# 1-Schematic_Arduino_Based_Weather_Statio.net
KiCad netlist of a schematic drawn in EasyEDA
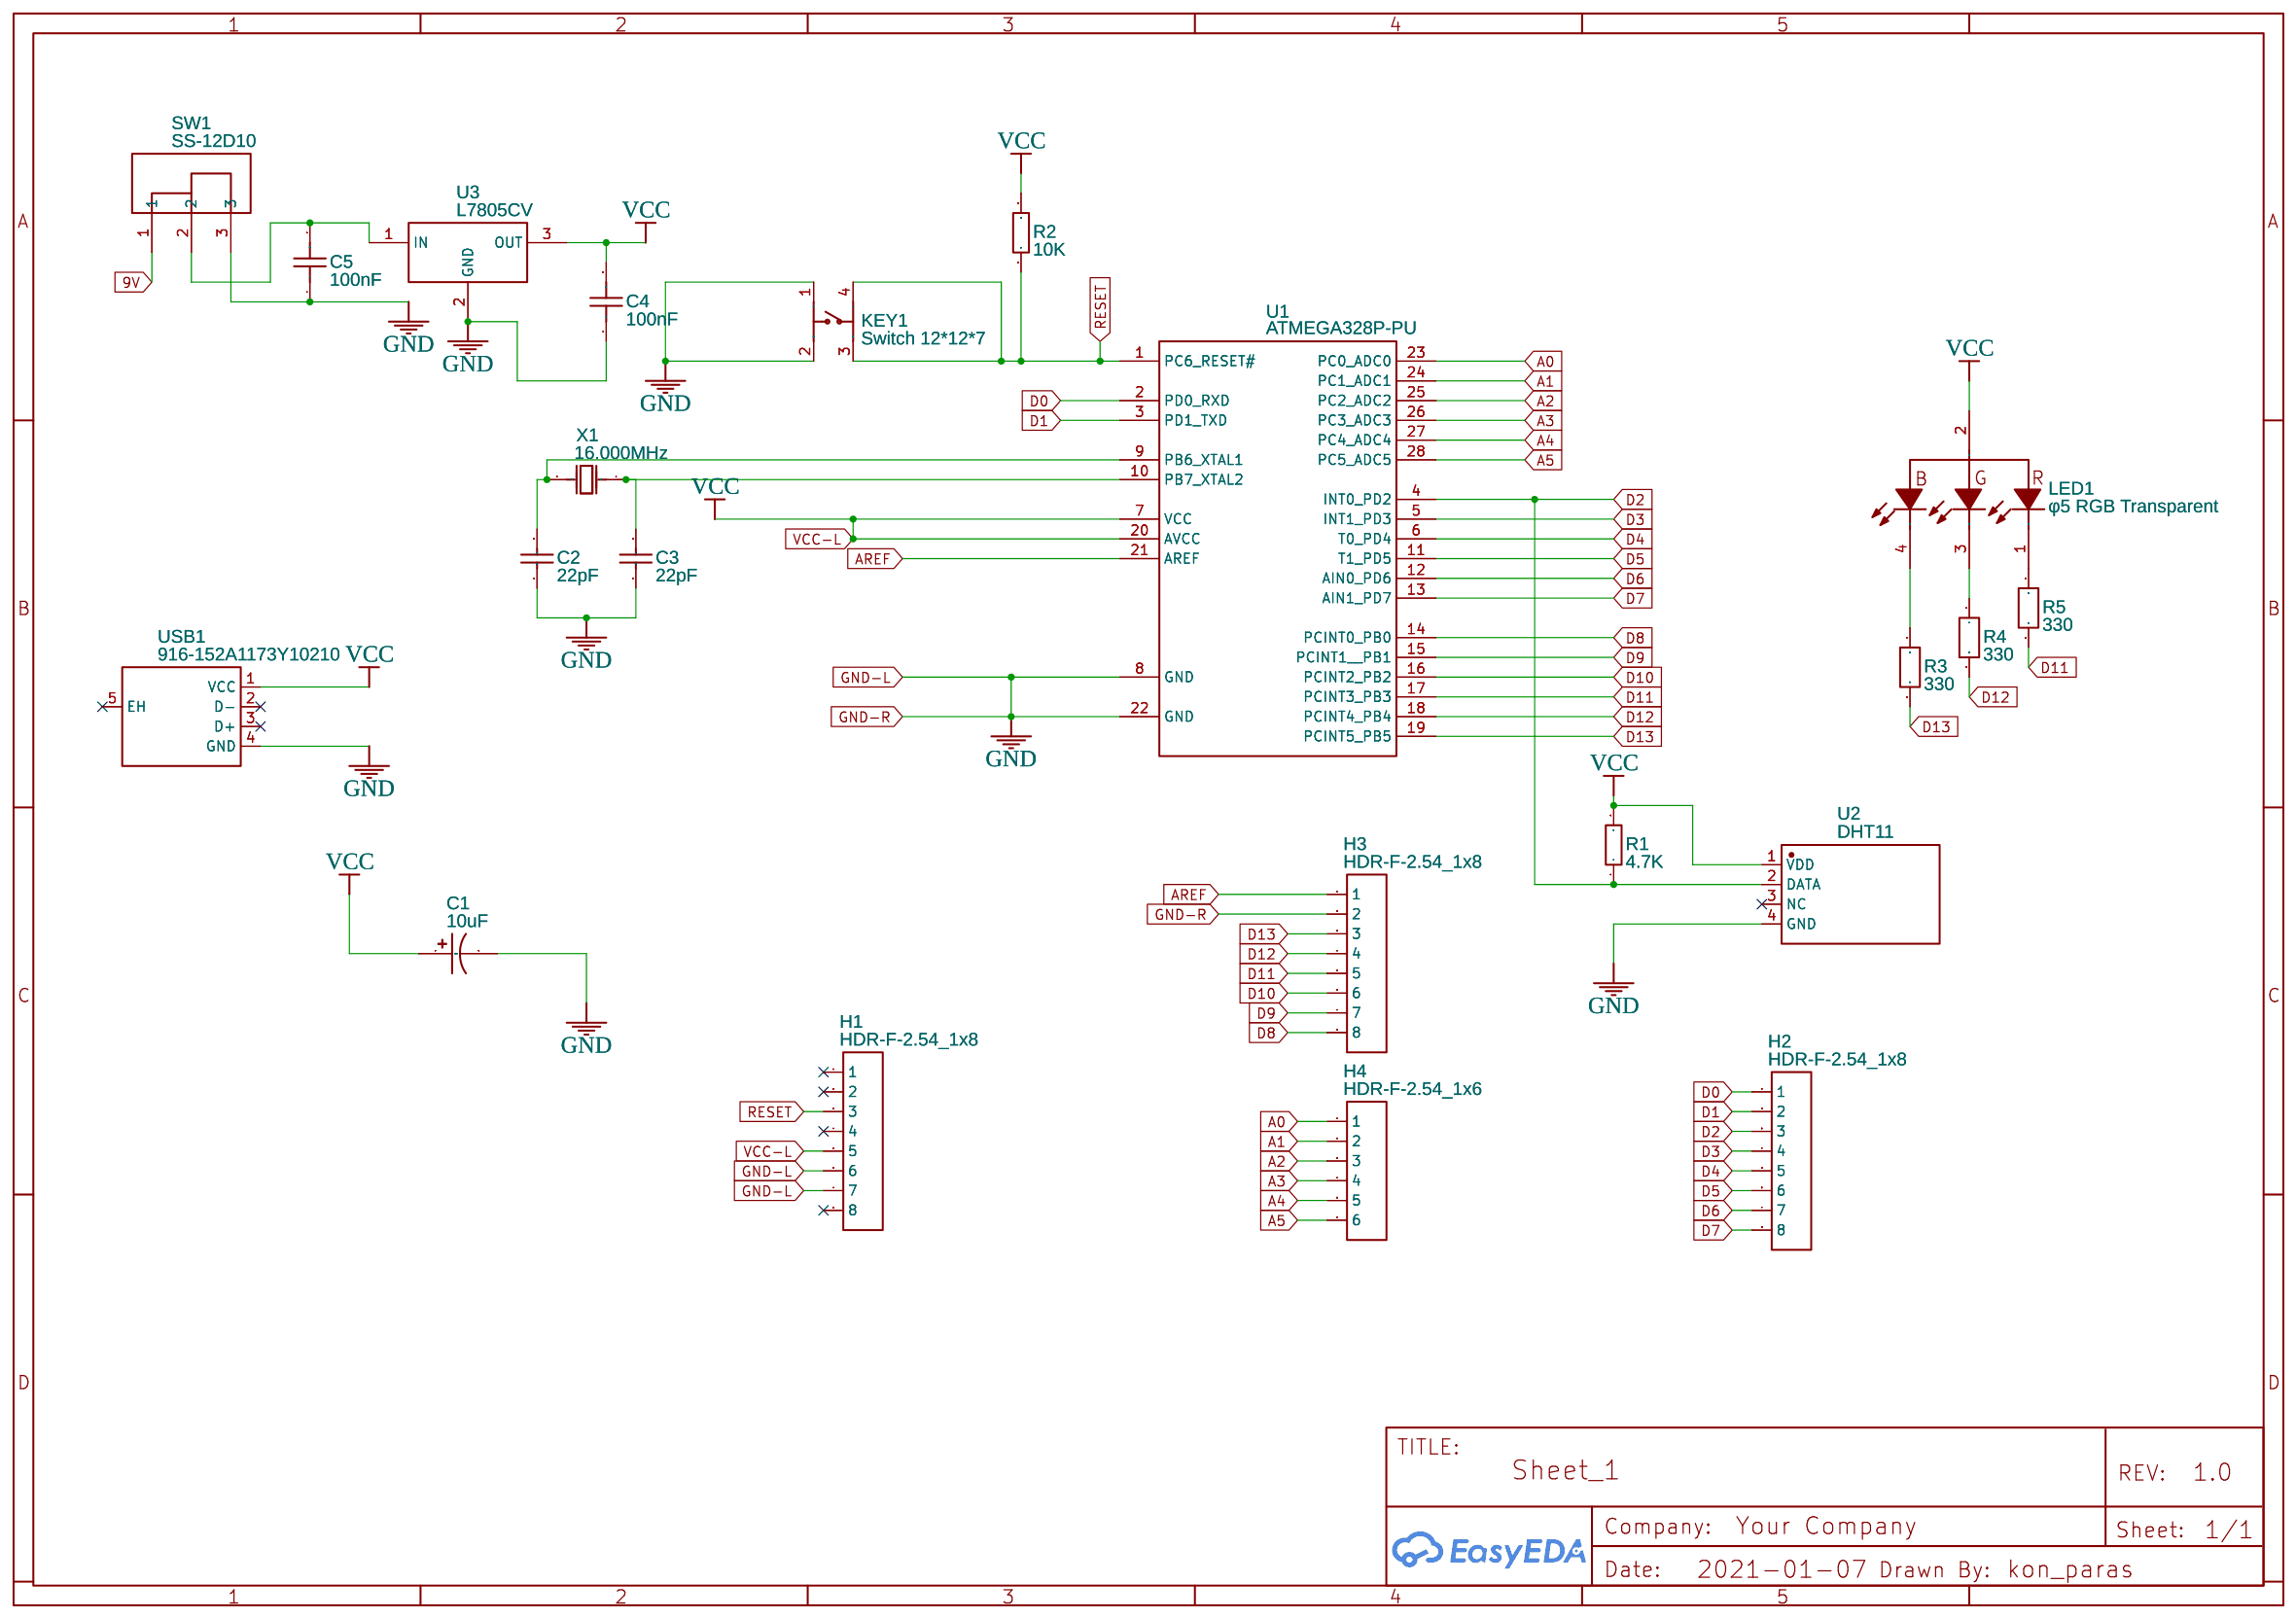
[diagram p0: schematic sheet]

(export (version "E")
  (design (tool "Eeschema 10.0.6"))
  (components
    (comp (ref "C1")
      (value "10uF")
      (fields
        (field (name "BOM_Manufacturer Part") "25MH710MEFCT55X7")
        (field (name "BOM_Supplier Part") "C473156")
      )
      (libsource (lib "") (part "25MH710MEFCT55X7"))
    )
    (comp (ref "C2")
      (value "22pF")
      (fields
        (field (name "BOM_Manufacturer Part") "L06S1B220KN0B0S0N0")
        (field (name "BOM_Supplier Part") "C260720")
      )
      (libsource (lib "") (part "L06S1B220KN0B0S0N0"))
    )
    (comp (ref "C3")
      (value "22pF")
      (fields
        (field (name "BOM_Manufacturer Part") "L06S1B220KN0B0S0N0")
        (field (name "BOM_Supplier Part") "C260720")
      )
      (libsource (lib "") (part "L06S1B220KN0B0S0N0"))
    )
    (comp (ref "C4")
      (value "100nF")
      (fields
        (field (name "BOM_Manufacturer Part") "CC1H104ZC1PD3F5P30MF")
        (field (name "BOM_Supplier Part") "C254069")
      )
      (libsource (lib "") (part "CC1H104ZC1PD3F5P30MF"))
    )
    (comp (ref "C5")
      (value "100nF")
      (fields
        (field (name "BOM_Manufacturer Part") "CC1H104ZC1PD3F5P30MF")
        (field (name "BOM_Supplier Part") "C254069")
      )
      (libsource (lib "") (part "CC1H104ZC1PD3F5P30MF"))
    )
    (comp (ref "H1")
      (value "HDR-F-2.54_1x8")
      (fields (field (name "BOM_Supplier Part") "C225505"))
      (libsource (lib "") (part "HDR-F-2.54_1x8"))
    )
    (comp (ref "H2")
      (value "HDR-F-2.54_1x8")
      (fields (field (name "BOM_Supplier Part") "C225505"))
      (libsource (lib "") (part "HDR-F-2.54_1x8"))
    )
    (comp (ref "H3")
      (value "HDR-F-2.54_1x8")
      (fields (field (name "BOM_Supplier Part") "C225505"))
      (libsource (lib "") (part "HDR-F-2.54_1x8"))
    )
    (comp (ref "H4")
      (value "HDR-F-2.54_1x6")
      (fields (field (name "BOM_Supplier Part") "C40877"))
      (libsource (lib "") (part "HDR-F-2.54_1x6"))
    )
    (comp (ref "KEY1")
      (value "Switch 12*12*7")
      (fields (field (name "BOM_Supplier Part") "C14248"))
      (libsource (lib "") (part "Switch 12*12*7"))
    )
    (comp (ref "LED1")
      (value "φ5 RGB Transparent")
      (fields
        (field (name "BOM_Manufacturer Part") "φ5 RGB Transparent LED")
        (field (name "BOM_Supplier Part") "C32985")
      )
      (libsource (lib "") (part "φ5 RGB Transparent"))
    )
    (comp (ref "R1")
      (value "4.7K")
      (fields
        (field (name "BOM_Manufacturer Part") "RD50T5472J")
        (field (name "BOM_Supplier Part") "C167584")
      )
      (libsource (lib "") (part "RD50T5472J"))
    )
    (comp (ref "R2")
      (value "10K")
      (fields
        (field (name "BOM_Manufacturer Part") "CFR0S2J0103A10")
        (field (name "BOM_Supplier Part") "C61283")
      )
      (libsource (lib "") (part "CFR0S2J0103A10"))
    )
    (comp (ref "R3")
      (value "330")
      (fields
        (field (name "BOM_Manufacturer Part") "RN 1/2WS 330R F T/B A1")
        (field (name "BOM_Supplier Part") "C433516")
      )
      (libsource (lib "") (part "RN 1/2WS 330R F T/B A1"))
    )
    (comp (ref "R4")
      (value "330")
      (fields
        (field (name "BOM_Manufacturer Part") "RN 1/2WS 330R F T/B A1")
        (field (name "BOM_Supplier Part") "C433516")
      )
      (libsource (lib "") (part "RN 1/2WS 330R F T/B A1"))
    )
    (comp (ref "R5")
      (value "330")
      (fields
        (field (name "BOM_Manufacturer Part") "RN 1/2WS 330R F T/B A1")
        (field (name "BOM_Supplier Part") "C433516")
      )
      (libsource (lib "") (part "RN 1/2WS 330R F T/B A1"))
    )
    (comp (ref "SW1")
      (value "SS-12D10")
      (fields (field (name "BOM_Supplier Part") "undefined"))
      (libsource (lib "") (part "SS-12D10"))
    )
    (comp (ref "U1")
      (value "ATMEGA328P-PU")
      (fields (field (name "BOM_Supplier Part") "C33901"))
      (libsource (lib "") (part "ATMEGA328P-PU"))
    )
    (comp (ref "U2")
      (value "DHT11")
      (fields (field (name "BOM_Supplier Part") "C117051"))
      (libsource (lib "") (part "DHT11"))
    )
    (comp (ref "U3")
      (value "L7805CV")
      (fields (field (name "BOM_Supplier Part") "C111887"))
      (libsource (lib "") (part "L7805CV"))
    )
    (comp (ref "USB1")
      (value "916-152A1173Y10210")
      (fields (field (name "BOM_Supplier Part") "C708918"))
      (libsource (lib "") (part "916-152A1173Y10210"))
    )
    (comp (ref "X1")
      (value "16.000MHz")
      (fields
        (field (name "BOM_Manufacturer Part") "X49SD110592MSD2SC")
        (field (name "BOM_Supplier Part") "C2203")
      )
      (libsource (lib "") (part "X49SD110592MSD2SC"))
    )
  )
  (nets
    (net (code "1") (name "9V") (class "Default")
      (node (ref "SW1") (pin "1") (pinfunction "1_1") (pintype "unspecified"))
    )
    (net (code "2") (name "A0") (class "Default")
      (node (ref "H4") (pin "1") (pinfunction "1_1") (pintype "input"))
      (node (ref "U1") (pin "23") (pinfunction "PC0_ADC0_23") (pintype "bidirectional"))
    )
    (net (code "3") (name "A1") (class "Default")
      (node (ref "H4") (pin "2") (pinfunction "2_2") (pintype "input"))
      (node (ref "U1") (pin "24") (pinfunction "PC1_ADC1_24") (pintype "bidirectional"))
    )
    (net (code "4") (name "A2") (class "Default")
      (node (ref "H4") (pin "3") (pinfunction "3_3") (pintype "input"))
      (node (ref "U1") (pin "25") (pinfunction "PC2_ADC2_25") (pintype "bidirectional"))
    )
    (net (code "5") (name "A3") (class "Default")
      (node (ref "H4") (pin "4") (pinfunction "4_4") (pintype "input"))
      (node (ref "U1") (pin "26") (pinfunction "PC3_ADC3_26") (pintype "bidirectional"))
    )
    (net (code "6") (name "A4") (class "Default")
      (node (ref "H4") (pin "5") (pinfunction "5_5") (pintype "input"))
      (node (ref "U1") (pin "27") (pinfunction "PC4_ADC4_27") (pintype "bidirectional"))
    )
    (net (code "7") (name "A5") (class "Default")
      (node (ref "H4") (pin "6") (pinfunction "6_6") (pintype "input"))
      (node (ref "U1") (pin "28") (pinfunction "PC5_ADC5_28") (pintype "bidirectional"))
    )
    (net (code "8") (name "AREF") (class "Default")
      (node (ref "H3") (pin "1") (pinfunction "1_1") (pintype "unspecified"))
      (node (ref "U1") (pin "21") (pinfunction "AREF_21") (pintype "passive"))
    )
    (net (code "9") (name "D0") (class "Default")
      (node (ref "H2") (pin "1") (pinfunction "1_1") (pintype "unspecified"))
      (node (ref "U1") (pin "2") (pinfunction "PD0_RXD_2") (pintype "bidirectional"))
    )
    (net (code "10") (name "D1") (class "Default")
      (node (ref "H2") (pin "2") (pinfunction "2_2") (pintype "unspecified"))
      (node (ref "U1") (pin "3") (pinfunction "PD1_TXD_3") (pintype "bidirectional"))
    )
    (net (code "11") (name "D2") (class "Default")
      (node (ref "H2") (pin "3") (pinfunction "3_3") (pintype "unspecified"))
      (node (ref "R1") (pin "1") (pinfunction "1_1") (pintype "unspecified"))
      (node (ref "U1") (pin "4") (pinfunction "INT0_PD2_4") (pintype "bidirectional"))
      (node (ref "U2") (pin "2") (pinfunction "DATA_2") (pintype "unspecified"))
    )
    (net (code "12") (name "D3") (class "Default")
      (node (ref "H2") (pin "4") (pinfunction "4_4") (pintype "unspecified"))
      (node (ref "U1") (pin "5") (pinfunction "INT1_PD3_5") (pintype "bidirectional"))
    )
    (net (code "13") (name "D4") (class "Default")
      (node (ref "H2") (pin "5") (pinfunction "5_5") (pintype "unspecified"))
      (node (ref "U1") (pin "6") (pinfunction "T0_PD4_6") (pintype "bidirectional"))
    )
    (net (code "14") (name "D5") (class "Default")
      (node (ref "H2") (pin "6") (pinfunction "6_6") (pintype "unspecified"))
      (node (ref "U1") (pin "11") (pinfunction "T1_PD5_11") (pintype "bidirectional"))
    )
    (net (code "15") (name "D6") (class "Default")
      (node (ref "H2") (pin "7") (pinfunction "7_7") (pintype "unspecified"))
      (node (ref "U1") (pin "12") (pinfunction "AIN0_PD6_12") (pintype "bidirectional"))
    )
    (net (code "16") (name "D7") (class "Default")
      (node (ref "H2") (pin "8") (pinfunction "8_8") (pintype "unspecified"))
      (node (ref "U1") (pin "13") (pinfunction "AIN1_PD7_13") (pintype "bidirectional"))
    )
    (net (code "17") (name "D8") (class "Default")
      (node (ref "H3") (pin "8") (pinfunction "8_8") (pintype "unspecified"))
      (node (ref "U1") (pin "14") (pinfunction "PCINT0_PB0_14") (pintype "bidirectional"))
    )
    (net (code "18") (name "D9") (class "Default")
      (node (ref "H3") (pin "7") (pinfunction "7_7") (pintype "unspecified"))
      (node (ref "U1") (pin "15") (pinfunction "PCINT1__PB1_15") (pintype "bidirectional"))
    )
    (net (code "19") (name "D10") (class "Default")
      (node (ref "H3") (pin "6") (pinfunction "6_6") (pintype "unspecified"))
      (node (ref "U1") (pin "16") (pinfunction "PCINT2_PB2_16") (pintype "bidirectional"))
    )
    (net (code "20") (name "D11") (class "Default")
      (node (ref "H3") (pin "5") (pinfunction "5_5") (pintype "unspecified"))
      (node (ref "R5") (pin "2") (pinfunction "2_2") (pintype "unspecified"))
      (node (ref "U1") (pin "17") (pinfunction "PCINT3_PB3_17") (pintype "bidirectional"))
    )
    (net (code "21") (name "D12") (class "Default")
      (node (ref "H3") (pin "4") (pinfunction "4_4") (pintype "unspecified"))
      (node (ref "R4") (pin "2") (pinfunction "2_2") (pintype "unspecified"))
      (node (ref "U1") (pin "18") (pinfunction "PCINT4_PB4_18") (pintype "bidirectional"))
    )
    (net (code "22") (name "D13") (class "Default")
      (node (ref "H3") (pin "3") (pinfunction "3_3") (pintype "unspecified"))
      (node (ref "R3") (pin "2") (pinfunction "2_2") (pintype "unspecified"))
      (node (ref "U1") (pin "19") (pinfunction "PCINT5_PB5_19") (pintype "bidirectional"))
    )
    (net (code "23") (name "GND-L") (class "Default")
      (node (ref "C1") (pin "2") (pinfunction "2_2") (pintype "unspecified"))
      (node (ref "C2") (pin "1") (pinfunction "1_1") (pintype "input"))
      (node (ref "C3") (pin "1") (pinfunction "1_1") (pintype "input"))
      (node (ref "C4") (pin "1") (pinfunction "1_1") (pintype "unspecified"))
      (node (ref "C5") (pin "1") (pinfunction "1_1") (pintype "unspecified"))
      (node (ref "H1") (pin "6") (pinfunction "6_6") (pintype "unspecified"))
      (node (ref "H1") (pin "7") (pinfunction "7_7") (pintype "unspecified"))
      (node (ref "H3") (pin "2") (pinfunction "2_2") (pintype "unspecified"))
      (node (ref "KEY1") (pin "1") (pinfunction "1_1") (pintype "unspecified"))
      (node (ref "KEY1") (pin "2") (pinfunction "2_2") (pintype "unspecified"))
      (node (ref "SW1") (pin "3") (pinfunction "3_3") (pintype "unspecified"))
      (node (ref "U1") (pin "22") (pinfunction "GND_22") (pintype "passive"))
      (node (ref "U1") (pin "8") (pinfunction "GND_8") (pintype "passive"))
      (node (ref "U2") (pin "4") (pinfunction "GND_4") (pintype "unspecified"))
      (node (ref "U3") (pin "2") (pinfunction "GND_2") (pintype "passive"))
      (node (ref "USB1") (pin "4") (pinfunction "GND_4") (pintype "input"))
    )
    (net (code "24") (name "Net-(LED1-KB)") (class "Default")
      (node (ref "LED1") (pin "4") (pinfunction "KB_4") (pintype "unspecified"))
      (node (ref "R3") (pin "1") (pinfunction "1_1") (pintype "unspecified"))
    )
    (net (code "25") (name "Net-(LED1-KG)") (class "Default")
      (node (ref "LED1") (pin "3") (pinfunction "KG_3") (pintype "unspecified"))
      (node (ref "R4") (pin "1") (pinfunction "1_1") (pintype "unspecified"))
    )
    (net (code "26") (name "Net-(LED1-KR)") (class "Default")
      (node (ref "LED1") (pin "1") (pinfunction "KR_1") (pintype "unspecified"))
      (node (ref "R5") (pin "1") (pinfunction "1_1") (pintype "unspecified"))
    )
    (net (code "27") (name "Net-(U1-PB6_XTAL1)") (class "Default")
      (node (ref "C2") (pin "2") (pinfunction "2_2") (pintype "input"))
      (node (ref "U1") (pin "9") (pinfunction "PB6_XTAL1_9") (pintype "bidirectional"))
      (node (ref "X1") (pin "2") (pinfunction "OSC2_2") (pintype "input"))
    )
    (net (code "28") (name "Net-(U1-PB7_XTAL2)") (class "Default")
      (node (ref "C3") (pin "2") (pinfunction "2_2") (pintype "input"))
      (node (ref "U1") (pin "10") (pinfunction "PB7_XTAL2_10") (pintype "bidirectional"))
      (node (ref "X1") (pin "1") (pinfunction "OSC1_1") (pintype "input"))
    )
    (net (code "29") (name "Net-(U3-IN)") (class "Default")
      (node (ref "C5") (pin "2") (pinfunction "2_2") (pintype "unspecified"))
      (node (ref "SW1") (pin "2") (pinfunction "2_2") (pintype "unspecified"))
      (node (ref "U3") (pin "1") (pinfunction "IN_1") (pintype "passive"))
    )
    (net (code "30") (name "RESET") (class "Default")
      (node (ref "H1") (pin "3") (pinfunction "3_3") (pintype "unspecified"))
      (node (ref "KEY1") (pin "3") (pinfunction "3_3") (pintype "unspecified"))
      (node (ref "KEY1") (pin "4") (pinfunction "4_4") (pintype "unspecified"))
      (node (ref "R2") (pin "1") (pinfunction "1_1") (pintype "input"))
      (node (ref "U1") (pin "1") (pinfunction "PC6_RESET#_1") (pintype "bidirectional"))
    )
    (net (code "31") (name "VCC-L") (class "Default")
      (node (ref "C1") (pin "1") (pinfunction "1_1") (pintype "unspecified"))
      (node (ref "C4") (pin "2") (pinfunction "2_2") (pintype "unspecified"))
      (node (ref "H1") (pin "5") (pinfunction "5_5") (pintype "unspecified"))
      (node (ref "LED1") (pin "2") (pinfunction "CA_2") (pintype "unspecified"))
      (node (ref "R1") (pin "2") (pinfunction "2_2") (pintype "unspecified"))
      (node (ref "R2") (pin "2") (pinfunction "2_2") (pintype "input"))
      (node (ref "U1") (pin "20") (pinfunction "AVCC_20") (pintype "passive"))
      (node (ref "U1") (pin "7") (pinfunction "VCC_7") (pintype "passive"))
      (node (ref "U2") (pin "1") (pinfunction "VDD_1") (pintype "unspecified"))
      (node (ref "U3") (pin "3") (pinfunction "OUT_3") (pintype "passive"))
      (node (ref "USB1") (pin "1") (pinfunction "VCC_1") (pintype "input"))
    )
    (net (code "32") (name "unconnected-(H1-Pad1)") (class "Default")
      (node (ref "H1") (pin "1") (pinfunction "1_1") (pintype "unspecified+no_connect"))
    )
    (net (code "33") (name "unconnected-(H1-Pad2)") (class "Default")
      (node (ref "H1") (pin "2") (pinfunction "2_2") (pintype "unspecified+no_connect"))
    )
    (net (code "34") (name "unconnected-(H1-Pad4)") (class "Default")
      (node (ref "H1") (pin "4") (pinfunction "4_4") (pintype "unspecified+no_connect"))
    )
    (net (code "35") (name "unconnected-(H1-Pad8)") (class "Default")
      (node (ref "H1") (pin "8") (pinfunction "8_8") (pintype "unspecified+no_connect"))
    )
    (net (code "36") (name "unconnected-(U2-NC-Pad3)") (class "Default")
      (node (ref "U2") (pin "3") (pinfunction "NC_3") (pintype "unspecified+no_connect"))
    )
    (net (code "37") (name "unconnected-(USB1-D+-Pad3)") (class "Default")
      (node (ref "USB1") (pin "3") (pinfunction "D+_3") (pintype "input+no_connect"))
    )
    (net (code "38") (name "unconnected-(USB1-D--Pad2)") (class "Default")
      (node (ref "USB1") (pin "2") (pinfunction "D-_2") (pintype "input+no_connect"))
    )
    (net (code "39") (name "unconnected-(USB1-EH-Pad5)") (class "Default")
      (node (ref "USB1") (pin "5") (pinfunction "EH_5") (pintype "unspecified+no_connect"))
    )
  )
)
